# I2C_switch.net
KiCad netlist of a schematic drawn in Altium Designer
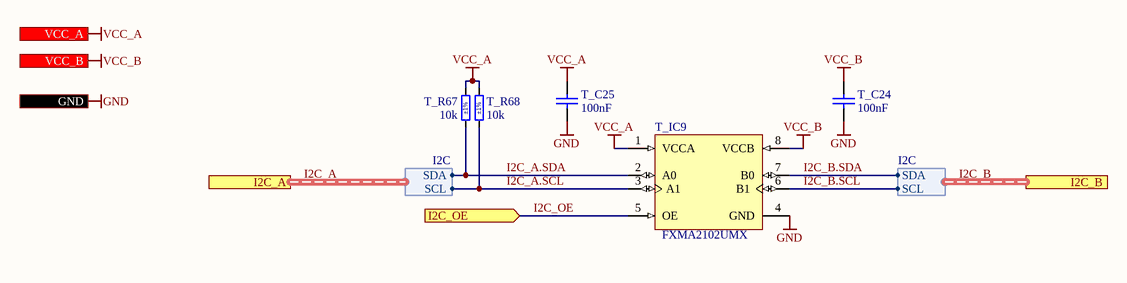
[diagram p0: I2C_switch.SchDoc]

(export (version "E")
  (design (tool "Eeschema 10.0.6"))
  (components
    (comp (ref "T_C24")
      (value "100nF")
      (footprint "CAPC1005X55N")
      (description "Non-polarised capacitor")
      (fields
        (field (name "PART NUMBER") "CC0402_100NF_16V_10%_X5R")
        (field (name "VOLTAGE") "16V")
        (field (name "AUTHOR") "CERN DEM JLC")
      )
      (libsource (lib "Capacitors") (part "Capacitor - non polarized"))
    )
    (comp (ref "T_C25")
      (value "100nF")
      (footprint "CAPC1005X55N")
      (description "Non-polarised capacitor")
      (fields
        (field (name "PART NUMBER") "CC0402_100NF_16V_10%_X5R")
        (field (name "VOLTAGE") "16V")
        (field (name "AUTHOR") "CERN DEM JLC")
      )
      (libsource (lib "Capacitors") (part "Capacitor - non polarized"))
    )
    (comp (ref "T_IC9")
      (value "FXMA2102UMX")
      (footprint "FXMA2102UMX")
      (description "Dual Supply 2-Bit Voltage Translator/Buffer/Repeater Isolator for I2C Applications")
      (fields (field (name "MANUFACTURER") "Onsemi"))
      (libsource (lib "TechnoSystem Workspace") (part "FXMA2102UMX"))
    )
    (comp (ref "T_R67")
      (value "10k")
      (footprint "RESC1005X40N")
      (description "Resistor - 1%")
      (fields
        (field (name "TOLERANCE") "±1%")
        (field (name "PART NUMBER") "R0402_10K_1%_0.0625W_100PPM")
        (field (name "POWER") "0.0625W")
        (field (name "AUTHOR") "CERN DEM JLC")
      )
      (libsource (lib "Resistors") (part "Resistor - 1%"))
    )
    (comp (ref "T_R68")
      (value "10k")
      (footprint "RESC1005X40N")
      (description "Resistor - 1%")
      (fields
        (field (name "TOLERANCE") "±1%")
        (field (name "PART NUMBER") "R0402_10K_1%_0.0625W_100PPM")
        (field (name "POWER") "0.0625W")
        (field (name "AUTHOR") "CERN DEM JLC")
      )
      (libsource (lib "Resistors") (part "Resistor - 1%"))
    )
  )
  (nets
    (net (code "3") (name "/I2C_A.SCL") (class "Default")
      (node (ref "T_IC9") (pin "3") (pinfunction "A1_3") (pintype "bidirectional"))
      (node (ref "T_R68") (pin "1") (pinfunction "1_1") (pintype "passive"))
    )
    (net (code "4") (name "/I2C_A.SDA") (class "Default")
      (node (ref "T_IC9") (pin "2") (pinfunction "A0_2") (pintype "bidirectional"))
      (node (ref "T_R67") (pin "1") (pinfunction "1_1") (pintype "passive"))
    )
    (net (code "6") (name "/I2C_B.SCL") (class "Default")
      (node (ref "T_IC9") (pin "6") (pinfunction "B1_6") (pintype "bidirectional"))
    )
    (net (code "7") (name "/I2C_B.SDA") (class "Default")
      (node (ref "T_IC9") (pin "7") (pinfunction "B0_7") (pintype "bidirectional"))
    )
    (net (code "9") (name "/I2C_OE") (class "Default")
      (node (ref "T_IC9") (pin "5") (pinfunction "OE_5") (pintype "input"))
    )
    (net (code "10") (name "GND") (class "Default")
      (node (ref "T_C24") (pin "1") (pinfunction "1_1") (pintype "passive"))
      (node (ref "T_C25") (pin "1") (pinfunction "1_1") (pintype "passive"))
      (node (ref "T_IC9") (pin "4") (pinfunction "GND_4") (pintype "power_in"))
    )
    (net (code "11") (name "VCC_A") (class "Default")
      (node (ref "T_C25") (pin "2") (pinfunction "2_2") (pintype "passive"))
      (node (ref "T_IC9") (pin "1") (pinfunction "VCCA_1") (pintype "input"))
      (node (ref "T_R67") (pin "2") (pinfunction "2_2") (pintype "passive"))
      (node (ref "T_R68") (pin "2") (pinfunction "2_2") (pintype "passive"))
    )
    (net (code "12") (name "VCC_B") (class "Default")
      (node (ref "T_C24") (pin "2") (pinfunction "2_2") (pintype "passive"))
      (node (ref "T_IC9") (pin "8") (pinfunction "VCCB_8") (pintype "input"))
    )
  )
)
